# MicroSD.net
KiCad netlist of a schematic drawn in Altium Designer
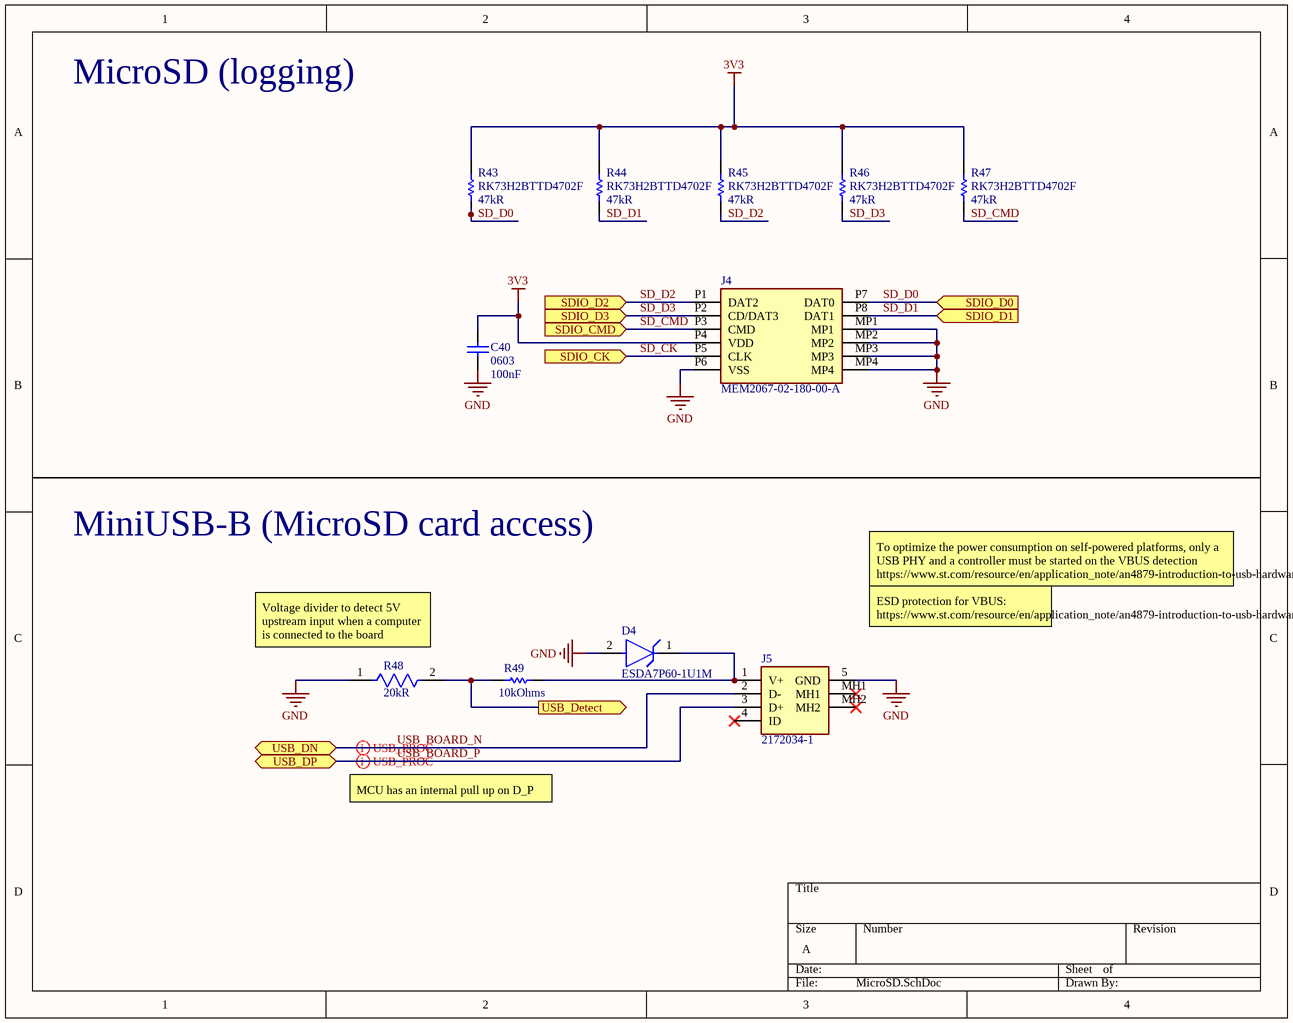
[diagram p0: MicroSD.SchDoc]

(export (version "E")
  (design (tool "Eeschema 10.0.6"))
  (components
    (comp (ref "C40")
      (value "C0603X104K5RACTU")
      (footprint "CAPC1608X87X35NL15T15")
      (fields
        (field (name "MANUFACTURER") "Kemet")
        (field (name "CASE CODE (IMPERIAL)") "0603")
        (field (name "CAPACITANCE") "100nF")
        (field (name "TOLERANCE") "10%")
        (field (name "VOLTAGE") "50V")
      )
      (libsource (lib "Altium Content Vault") (part "CAP"))
    )
    (comp (ref "D4")
      (value "ESDA7P60-1U1M")
      (footprint "FP-1610-MFG")
      (description "TVS DIODE 5V 11.6V 1610")
      (fields
        (field (name "MANUFACTURER") "STMicroelectronics")
        (field (name "OCTOPART") "https://octopart.com/esda7p60-1u1m-stmicroelectronics-52112702")
      )
      (libsource (lib "Altium Content Vault") (part "f813f71cba58e380607f5dd3caf9714"))
    )
    (comp (ref "J4")
      (value "MEM2067-02-180-00-A")
      (footprint "SamacSys:MEM20670218000A")
      (description "Connector")
      (fields (field (name "MOUSER PART NUMBER") "640-MEM20670218000A"))
      (libsource (lib "*") (part "MEM2067-02-180-00-A"))
    )
    (comp (ref "J5")
      (value "2172034-1")
      (footprint "SamacSys:21720341")
      (description "Connector")
      (fields (field (name "MOUSER PART NUMBER") "571-2172034-1"))
      (libsource (lib "*") (part "2172034-1"))
    )
    (comp (ref "R43")
      (value "RK73H2BTTD4702F")
      (footprint "RESC3216X70X40NL20T20")
      (fields (field (name "MANUFACTURER") "KOA Speer") (field (name "ALTIUM_VALUE") "47kR"))
      (libsource (lib "Altium Content Vault") (part "RES"))
    )
    (comp (ref "R44")
      (value "RK73H2BTTD4702F")
      (footprint "RESC3216X70X40NL20T20")
      (fields (field (name "MANUFACTURER") "KOA Speer") (field (name "ALTIUM_VALUE") "47kR"))
      (libsource (lib "Altium Content Vault") (part "RES"))
    )
    (comp (ref "R45")
      (value "RK73H2BTTD4702F")
      (footprint "RESC3216X70X40NL20T20")
      (fields (field (name "MANUFACTURER") "KOA Speer") (field (name "ALTIUM_VALUE") "47kR"))
      (libsource (lib "Altium Content Vault") (part "RES"))
    )
    (comp (ref "R46")
      (value "RK73H2BTTD4702F")
      (footprint "RESC3216X70X40NL20T20")
      (fields (field (name "MANUFACTURER") "KOA Speer") (field (name "ALTIUM_VALUE") "47kR"))
      (libsource (lib "Altium Content Vault") (part "RES"))
    )
    (comp (ref "R47")
      (value "RK73H2BTTD4702F")
      (footprint "RESC3216X70X40NL20T20")
      (fields (field (name "MANUFACTURER") "KOA Speer") (field (name "ALTIUM_VALUE") "47kR"))
      (libsource (lib "Altium Content Vault") (part "RES"))
    )
    (comp (ref "R48")
      (value "CRCW080520K0JNEB")
      (footprint "FP-CRCW0805-e3-IPC_B")
      (description "RES Thick Film, 20kΩ, 5%, 0.125W, 200ppm/°C, 0805")
      (fields (field (name "RESISTANCE") "20kR") (field (name "TOLERANCE") "5%"))
      (libsource (lib "Altium Content Vault") (part "1029c3af85768c4190bb7ad29bc67b5"))
    )
    (comp (ref "R49")
      (value "RC0603JR-0710KL")
      (footprint "RESC1608X55X25ML10T15")
      (description "Resistor, 10 KOhm, +/- 5%, 100 mW, -55 to 155 degC, 0603 (1608 Metric), RoHS, Tape and Reel")
      (fields
        (field (name "RESISTANCE") "10kOhms")
        (field (name "MANUFACTURER") "Yageo")
        (field (name "TOLERANCE") "5%")
      )
      (libsource (lib "Altium Content Vault") (part "RES-2"))
    )
  )
  (nets
    (net (code "1") (name "/SD_CK") (class "Default")
      (node (ref "J4") (pin "P5") (pinfunction "CLK_P5") (pintype "passive"))
    )
    (net (code "2") (name "/SD_CMD") (class "Default")
      (node (ref "J4") (pin "P3") (pinfunction "CMD_P3") (pintype "passive"))
      (node (ref "R47") (pin "1") (pinfunction "1_1") (pintype "passive"))
    )
    (net (code "3") (name "/SD_D0") (class "Default")
      (node (ref "J4") (pin "P7") (pinfunction "DAT0_P7") (pintype "passive"))
      (node (ref "R43") (pin "1") (pinfunction "1_1") (pintype "passive"))
    )
    (net (code "4") (name "/SD_D1") (class "Default")
      (node (ref "J4") (pin "P8") (pinfunction "DAT1_P8") (pintype "passive"))
      (node (ref "R44") (pin "1") (pinfunction "1_1") (pintype "passive"))
    )
    (net (code "5") (name "/SD_D2") (class "Default")
      (node (ref "J4") (pin "P1") (pinfunction "DAT2_P1") (pintype "passive"))
      (node (ref "R45") (pin "1") (pinfunction "1_1") (pintype "passive"))
    )
    (net (code "6") (name "/SD_D3") (class "Default")
      (node (ref "J4") (pin "P2") (pinfunction "CD/DAT3_P2") (pintype "passive"))
      (node (ref "R46") (pin "1") (pinfunction "1_1") (pintype "passive"))
    )
    (net (code "7") (name "/USB_BOARD_N") (class "Default")
      (node (ref "J5") (pin "2") (pinfunction "D-_2") (pintype "passive"))
    )
    (net (code "8") (name "/USB_BOARD_P") (class "Default")
      (node (ref "J5") (pin "3") (pinfunction "D+_3") (pintype "passive"))
    )
    (net (code "9") (name "/USB_Detect") (class "Default")
      (node (ref "R48") (pin "2") (pinfunction "2_2") (pintype "passive"))
      (node (ref "R49") (pin "1") (pinfunction "1_1") (pintype "passive"))
    )
    (net (code "10") (name "3V3") (class "Default")
      (node (ref "C40") (pin "1") (pinfunction "1_1") (pintype "passive"))
      (node (ref "J4") (pin "P4") (pinfunction "VDD_P4") (pintype "passive"))
      (node (ref "R43") (pin "2") (pinfunction "2_2") (pintype "passive"))
      (node (ref "R44") (pin "2") (pinfunction "2_2") (pintype "passive"))
      (node (ref "R45") (pin "2") (pinfunction "2_2") (pintype "passive"))
      (node (ref "R46") (pin "2") (pinfunction "2_2") (pintype "passive"))
      (node (ref "R47") (pin "2") (pinfunction "2_2") (pintype "passive"))
    )
    (net (code "11") (name "GND") (class "Default")
      (node (ref "C40") (pin "2") (pinfunction "2_2") (pintype "passive"))
      (node (ref "D4") (pin "2") (pinfunction "A_2") (pintype "passive"))
      (node (ref "J4") (pin "MP1") (pinfunction "MP1_MP1") (pintype "passive"))
      (node (ref "J4") (pin "MP2") (pinfunction "MP2_MP2") (pintype "passive"))
      (node (ref "J4") (pin "MP3") (pinfunction "MP3_MP3") (pintype "passive"))
      (node (ref "J4") (pin "MP4") (pinfunction "MP4_MP4") (pintype "passive"))
      (node (ref "J4") (pin "P6") (pinfunction "VSS_P6") (pintype "passive"))
      (node (ref "J5") (pin "5") (pinfunction "GND_5") (pintype "passive"))
      (node (ref "R48") (pin "1") (pinfunction "1_1") (pintype "passive"))
    )
    (net (code "12") (name "Net-(D4-C)") (class "Default")
      (node (ref "D4") (pin "1") (pinfunction "C_1") (pintype "passive"))
      (node (ref "J5") (pin "1") (pinfunction "V+_1") (pintype "passive"))
      (node (ref "R49") (pin "2") (pinfunction "2_2") (pintype "passive"))
    )
    (net (code "13") (name "unconnected-(J5-ID-Pad4)") (class "Default")
      (node (ref "J5") (pin "4") (pinfunction "ID_4") (pintype "passive+no_connect"))
    )
    (net (code "14") (name "unconnected-(J5-PadMH1)") (class "Default")
      (node (ref "J5") (pin "MH1") (pinfunction "MH1_MH1") (pintype "passive+no_connect"))
    )
    (net (code "15") (name "unconnected-(J5-PadMH2)") (class "Default")
      (node (ref "J5") (pin "MH2") (pinfunction "MH2_MH2") (pintype "passive+no_connect"))
    )
  )
)
